# SparkFun_Uno_Qwiic_Mux_Shield_with_JST.net
KiCad netlist of a schematic drawn in EAGLE
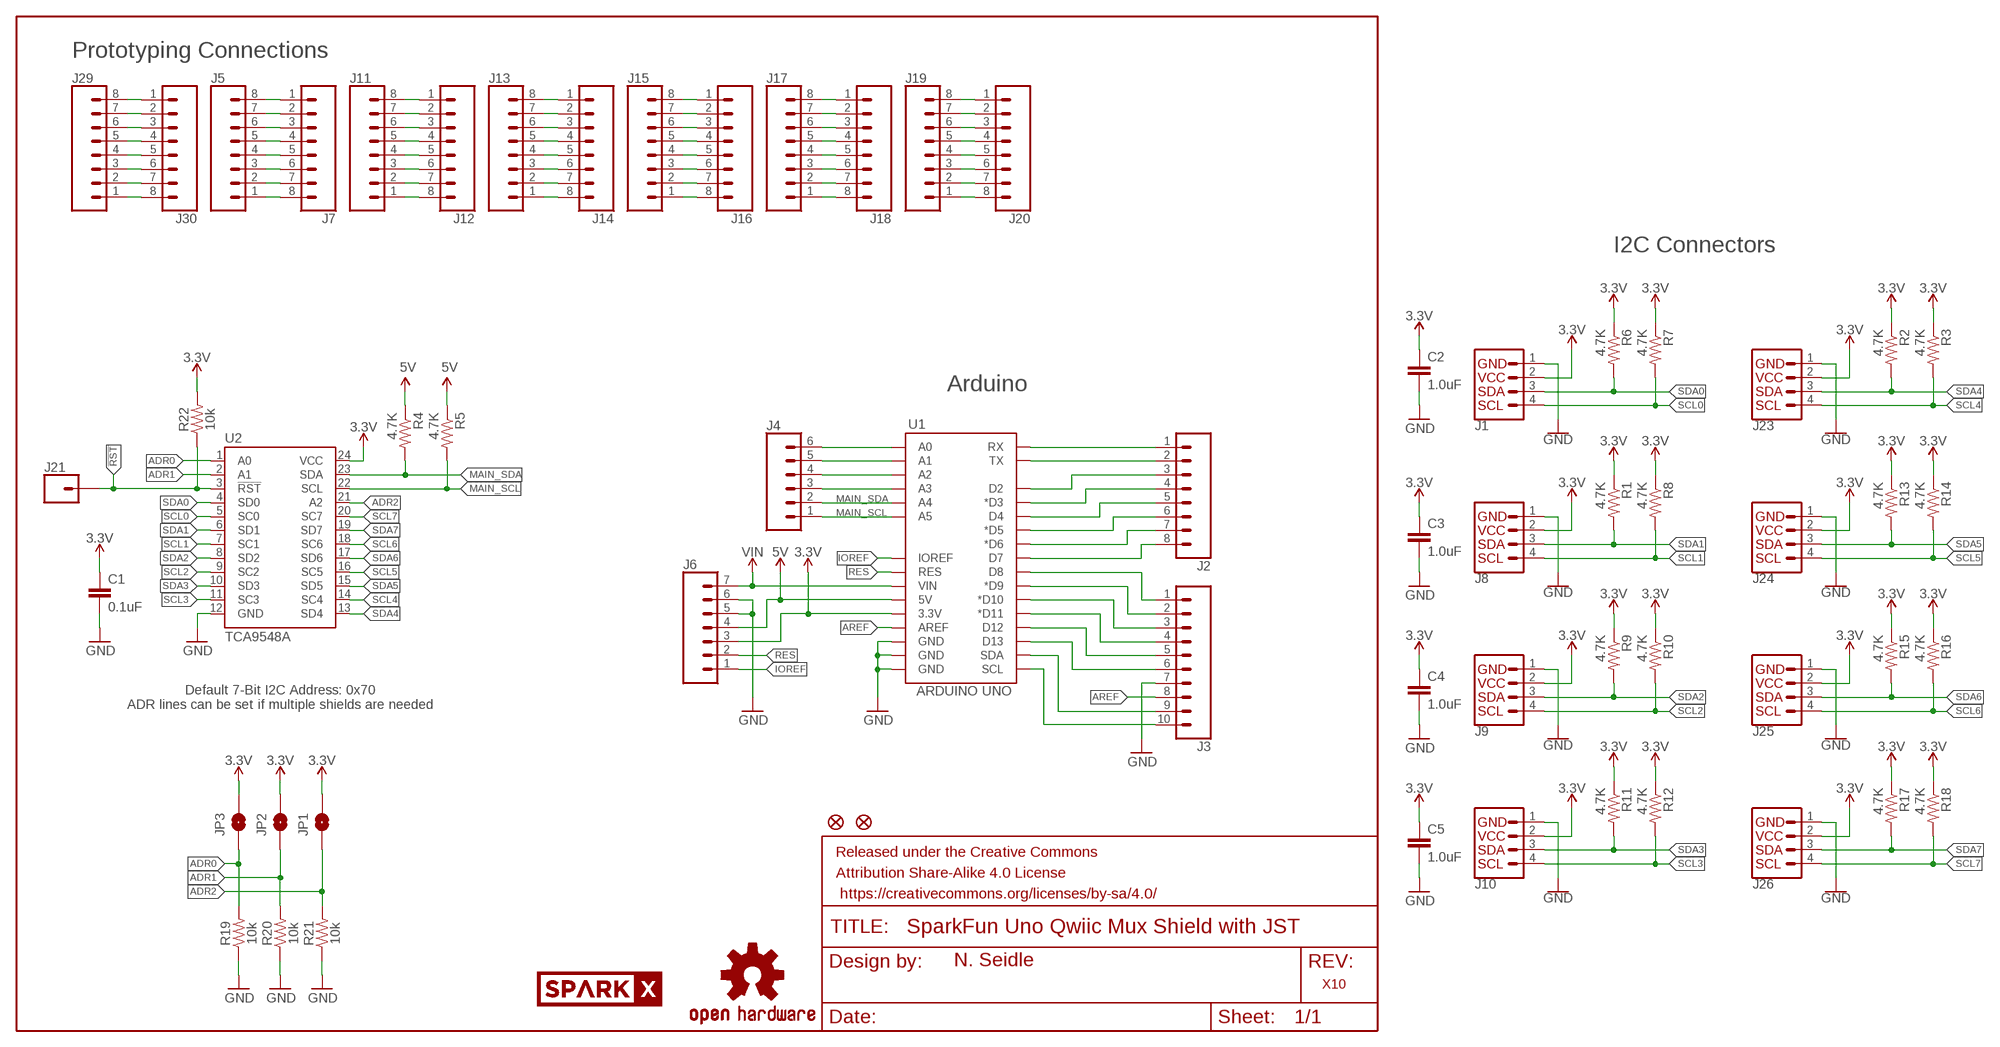
[diagram p0: schematic, sheet 1]

(export (version "E")
  (design (tool "Eeschema 10.0.6"))
  (components
    (comp (ref "C1")
      (value "0.1uF")
      (footprint "eagle-import:0603")
      (libsource (lib "eagle-import") (part "0.1UF-0603-25V-(+80/-20%)"))
    )
    (comp (ref "C2")
      (value "1.0uF")
      (footprint "eagle-import:0603")
      (libsource (lib "eagle-import") (part "1.0UF-0603-16V-10%"))
    )
    (comp (ref "C3")
      (value "1.0uF")
      (footprint "eagle-import:0603")
      (libsource (lib "eagle-import") (part "1.0UF-0603-16V-10%"))
    )
    (comp (ref "C4")
      (value "1.0uF")
      (footprint "eagle-import:0603")
      (libsource (lib "eagle-import") (part "1.0UF-0603-16V-10%"))
    )
    (comp (ref "C5")
      (value "1.0uF")
      (footprint "eagle-import:0603")
      (libsource (lib "eagle-import") (part "1.0UF-0603-16V-10%"))
    )
    (comp (ref "FD1")
      (value "FIDUCIAL1X2")
      (footprint "eagle-import:FIDUCIAL-1X2")
      (libsource (lib "eagle-import") (part "FIDUCIAL1X2"))
    )
    (comp (ref "FD2")
      (value "FIDUCIAL1X2")
      (footprint "eagle-import:FIDUCIAL-1X2")
      (libsource (lib "eagle-import") (part "FIDUCIAL1X2"))
    )
    (comp (ref "FRAME1")
      (value "FRAME-LETTER")
      (footprint "eagle-import:CREATIVE_COMMONS")
      (libsource (lib "eagle-import") (part "FRAME-LETTER"))
    )
    (comp (ref "J1")
      (value "I2C_STANDARDJS-1MM")
      (footprint "eagle-import:1X04_1MM_RA")
      (libsource (lib "eagle-import") (part "I2C_STANDARDJS-1MM"))
    )
    (comp (ref "J2")
      (value "CONN_08NO_SILK_FEMALE_PTH")
      (footprint "eagle-import:1X08_NO_SILK")
      (libsource (lib "eagle-import") (part "CONN_08NO_SILK_FEMALE_PTH"))
    )
    (comp (ref "J3")
      (value "CONN_10NO_SILK_PTH_FEMALE")
      (footprint "eagle-import:1X10_NO_SILK")
      (libsource (lib "eagle-import") (part "CONN_10NO_SILK_PTH_FEMALE"))
    )
    (comp (ref "J4")
      (value "CONN_06NO_SILK_FEMALE_PTH")
      (footprint "eagle-import:1X06_NO_SILK")
      (libsource (lib "eagle-import") (part "CONN_06NO_SILK_FEMALE_PTH"))
    )
    (comp (ref "J5")
      (value "CONN_08NO_SILK_FEMALE_PTH")
      (footprint "eagle-import:1X08_NO_SILK")
      (libsource (lib "eagle-import") (part "CONN_08NO_SILK_FEMALE_PTH"))
    )
    (comp (ref "J6")
      (value "CONN_07NO_SILK")
      (footprint "eagle-import:1X07_NO_SILK")
      (libsource (lib "eagle-import") (part "CONN_07NO_SILK"))
    )
    (comp (ref "J7")
      (value "CONN_08NO_SILK_FEMALE_PTH")
      (footprint "eagle-import:1X08_NO_SILK")
      (libsource (lib "eagle-import") (part "CONN_08NO_SILK_FEMALE_PTH"))
    )
    (comp (ref "J8")
      (value "I2C_STANDARDJS-1MM")
      (footprint "eagle-import:1X04_1MM_RA")
      (libsource (lib "eagle-import") (part "I2C_STANDARDJS-1MM"))
    )
    (comp (ref "J9")
      (value "I2C_STANDARDJS-1MM")
      (footprint "eagle-import:1X04_1MM_RA")
      (libsource (lib "eagle-import") (part "I2C_STANDARDJS-1MM"))
    )
    (comp (ref "J10")
      (value "I2C_STANDARDJS-1MM")
      (footprint "eagle-import:1X04_1MM_RA")
      (libsource (lib "eagle-import") (part "I2C_STANDARDJS-1MM"))
    )
    (comp (ref "J11")
      (value "CONN_08NO_SILK_FEMALE_PTH")
      (footprint "eagle-import:1X08_NO_SILK")
      (libsource (lib "eagle-import") (part "CONN_08NO_SILK_FEMALE_PTH"))
    )
    (comp (ref "J12")
      (value "CONN_08NO_SILK_FEMALE_PTH")
      (footprint "eagle-import:1X08_NO_SILK")
      (libsource (lib "eagle-import") (part "CONN_08NO_SILK_FEMALE_PTH"))
    )
    (comp (ref "J13")
      (value "CONN_08NO_SILK_FEMALE_PTH")
      (footprint "eagle-import:1X08_NO_SILK")
      (libsource (lib "eagle-import") (part "CONN_08NO_SILK_FEMALE_PTH"))
    )
    (comp (ref "J14")
      (value "CONN_08NO_SILK_FEMALE_PTH")
      (footprint "eagle-import:1X08_NO_SILK")
      (libsource (lib "eagle-import") (part "CONN_08NO_SILK_FEMALE_PTH"))
    )
    (comp (ref "J15")
      (value "CONN_08NO_SILK_FEMALE_PTH")
      (footprint "eagle-import:1X08_NO_SILK")
      (libsource (lib "eagle-import") (part "CONN_08NO_SILK_FEMALE_PTH"))
    )
    (comp (ref "J16")
      (value "CONN_08NO_SILK_FEMALE_PTH")
      (footprint "eagle-import:1X08_NO_SILK")
      (libsource (lib "eagle-import") (part "CONN_08NO_SILK_FEMALE_PTH"))
    )
    (comp (ref "J17")
      (value "CONN_08NO_SILK_FEMALE_PTH")
      (footprint "eagle-import:1X08_NO_SILK")
      (libsource (lib "eagle-import") (part "CONN_08NO_SILK_FEMALE_PTH"))
    )
    (comp (ref "J18")
      (value "CONN_08NO_SILK_FEMALE_PTH")
      (footprint "eagle-import:1X08_NO_SILK")
      (libsource (lib "eagle-import") (part "CONN_08NO_SILK_FEMALE_PTH"))
    )
    (comp (ref "J19")
      (value "CONN_08NO_SILK_FEMALE_PTH")
      (footprint "eagle-import:1X08_NO_SILK")
      (libsource (lib "eagle-import") (part "CONN_08NO_SILK_FEMALE_PTH"))
    )
    (comp (ref "J20")
      (value "CONN_08NO_SILK_FEMALE_PTH")
      (footprint "eagle-import:1X08_NO_SILK")
      (libsource (lib "eagle-import") (part "CONN_08NO_SILK_FEMALE_PTH"))
    )
    (comp (ref "J21")
      (value "CONN_01")
      (footprint "eagle-import:1X01")
      (libsource (lib "eagle-import") (part "CONN_01"))
    )
    (comp (ref "J23")
      (value "I2C_STANDARDSILK")
      (footprint "eagle-import:1X04")
      (libsource (lib "eagle-import") (part "I2C_STANDARDSILK"))
    )
    (comp (ref "J24")
      (value "I2C_STANDARDSILK")
      (footprint "eagle-import:1X04")
      (libsource (lib "eagle-import") (part "I2C_STANDARDSILK"))
    )
    (comp (ref "J25")
      (value "I2C_STANDARDSILK")
      (footprint "eagle-import:1X04")
      (libsource (lib "eagle-import") (part "I2C_STANDARDSILK"))
    )
    (comp (ref "J26")
      (value "I2C_STANDARDSILK")
      (footprint "eagle-import:1X04")
      (libsource (lib "eagle-import") (part "I2C_STANDARDSILK"))
    )
    (comp (ref "J29")
      (value "CONN_08NO_SILK_FEMALE_PTH")
      (footprint "eagle-import:1X08_NO_SILK")
      (libsource (lib "eagle-import") (part "CONN_08NO_SILK_FEMALE_PTH"))
    )
    (comp (ref "J30")
      (value "CONN_08NO_SILK_FEMALE_PTH")
      (footprint "eagle-import:1X08_NO_SILK")
      (libsource (lib "eagle-import") (part "CONN_08NO_SILK_FEMALE_PTH"))
    )
    (comp (ref "JP1")
      (value "JUMPER-SMT_2_NO_SILK")
      (footprint "eagle-import:SMT-JUMPER_2_NO_SILK")
      (libsource (lib "eagle-import") (part "JUMPER-SMT_2_NO_SILK"))
    )
    (comp (ref "JP2")
      (value "JUMPER-SMT_2_NO_SILK")
      (footprint "eagle-import:SMT-JUMPER_2_NO_SILK")
      (libsource (lib "eagle-import") (part "JUMPER-SMT_2_NO_SILK"))
    )
    (comp (ref "JP3")
      (value "JUMPER-SMT_2_NO_SILK")
      (footprint "eagle-import:SMT-JUMPER_2_NO_SILK")
      (libsource (lib "eagle-import") (part "JUMPER-SMT_2_NO_SILK"))
    )
    (comp (ref "LOGO1")
      (value "OSHW-LOGOMINI")
      (footprint "eagle-import:OSHW-LOGO-MINI")
      (libsource (lib "eagle-import") (part "OSHW-LOGOMINI"))
    )
    (comp (ref "R1")
      (value "4.7K")
      (footprint "eagle-import:0603-RES")
      (libsource (lib "eagle-import") (part "4.7KOHM-1/10W-1%(0603)"))
    )
    (comp (ref "R2")
      (value "4.7K")
      (footprint "eagle-import:0603-RES")
      (libsource (lib "eagle-import") (part "4.7KOHM-1/10W-1%(0603)"))
    )
    (comp (ref "R3")
      (value "4.7K")
      (footprint "eagle-import:0603-RES")
      (libsource (lib "eagle-import") (part "4.7KOHM-1/10W-1%(0603)"))
    )
    (comp (ref "R4")
      (value "4.7K")
      (footprint "eagle-import:0603-RES")
      (libsource (lib "eagle-import") (part "4.7KOHM-1/10W-1%(0603)"))
    )
    (comp (ref "R5")
      (value "4.7K")
      (footprint "eagle-import:0603-RES")
      (libsource (lib "eagle-import") (part "4.7KOHM-1/10W-1%(0603)"))
    )
    (comp (ref "R6")
      (value "4.7K")
      (footprint "eagle-import:0603-RES")
      (libsource (lib "eagle-import") (part "4.7KOHM-1/10W-1%(0603)"))
    )
    (comp (ref "R7")
      (value "4.7K")
      (footprint "eagle-import:0603-RES")
      (libsource (lib "eagle-import") (part "4.7KOHM-1/10W-1%(0603)"))
    )
    (comp (ref "R8")
      (value "4.7K")
      (footprint "eagle-import:0603-RES")
      (libsource (lib "eagle-import") (part "4.7KOHM-1/10W-1%(0603)"))
    )
    (comp (ref "R9")
      (value "4.7K")
      (footprint "eagle-import:0603-RES")
      (libsource (lib "eagle-import") (part "4.7KOHM-1/10W-1%(0603)"))
    )
    (comp (ref "R10")
      (value "4.7K")
      (footprint "eagle-import:0603-RES")
      (libsource (lib "eagle-import") (part "4.7KOHM-1/10W-1%(0603)"))
    )
    (comp (ref "R11")
      (value "4.7K")
      (footprint "eagle-import:0603-RES")
      (libsource (lib "eagle-import") (part "4.7KOHM-1/10W-1%(0603)"))
    )
    (comp (ref "R12")
      (value "4.7K")
      (footprint "eagle-import:0603-RES")
      (libsource (lib "eagle-import") (part "4.7KOHM-1/10W-1%(0603)"))
    )
    (comp (ref "R13")
      (value "4.7K")
      (footprint "eagle-import:0603-RES")
      (libsource (lib "eagle-import") (part "4.7KOHM-1/10W-1%(0603)"))
    )
    (comp (ref "R14")
      (value "4.7K")
      (footprint "eagle-import:0603-RES")
      (libsource (lib "eagle-import") (part "4.7KOHM-1/10W-1%(0603)"))
    )
    (comp (ref "R15")
      (value "4.7K")
      (footprint "eagle-import:0603-RES")
      (libsource (lib "eagle-import") (part "4.7KOHM-1/10W-1%(0603)"))
    )
    (comp (ref "R16")
      (value "4.7K")
      (footprint "eagle-import:0603-RES")
      (libsource (lib "eagle-import") (part "4.7KOHM-1/10W-1%(0603)"))
    )
    (comp (ref "R17")
      (value "4.7K")
      (footprint "eagle-import:0603-RES")
      (libsource (lib "eagle-import") (part "4.7KOHM-1/10W-1%(0603)"))
    )
    (comp (ref "R18")
      (value "4.7K")
      (footprint "eagle-import:0603-RES")
      (libsource (lib "eagle-import") (part "4.7KOHM-1/10W-1%(0603)"))
    )
    (comp (ref "R19")
      (value "10k")
      (footprint "eagle-import:0603")
      (libsource (lib "eagle-import") (part "10KOHM-0603-1/10W-1%"))
    )
    (comp (ref "R20")
      (value "10k")
      (footprint "eagle-import:0603")
      (libsource (lib "eagle-import") (part "10KOHM-0603-1/10W-1%"))
    )
    (comp (ref "R21")
      (value "10k")
      (footprint "eagle-import:0603")
      (libsource (lib "eagle-import") (part "10KOHM-0603-1/10W-1%"))
    )
    (comp (ref "R22")
      (value "10k")
      (footprint "eagle-import:0603")
      (libsource (lib "eagle-import") (part "10KOHM-0603-1/10W-1%"))
    )
    (comp (ref "U$1")
      (value "SPARKX-LOGO3")
      (footprint "eagle-import:SPARKX-SMALL")
      (libsource (lib "eagle-import") (part "SPARKX-LOGO3"))
    )
    (comp (ref "U$2")
      (value "SPARKX-LOGO5")
      (footprint "eagle-import:SPARKX-LARGE")
      (libsource (lib "eagle-import") (part "SPARKX-LOGO5"))
    )
    (comp (ref "U1")
      (value "ARDUINO UNO")
      (footprint "eagle-import:UNO_R3_SHIELD_NOLABELS")
      (libsource (lib "eagle-import") (part "ARDUINO_R3_SHIELDNOLABELS"))
    )
    (comp (ref "U2")
      (value "TCA9548A")
      (footprint "eagle-import:TSSOP28")
      (libsource (lib "eagle-import") (part "TCA9548A"))
    )
  )
  (nets
    (net (code "1") (name "/~{RST}") (class "Default")
      (node (ref "J21") (pin "1") (pinfunction "1_1") (pintype "passive"))
      (node (ref "R22") (pin "1") (pinfunction "1_1") (pintype "passive"))
      (node (ref "U2") (pin "3") (pinfunction "~{RST}_3") (pintype "bidirectional"))
    )
    (net (code "2") (name "3.3V") (class "Default")
      (node (ref "C1") (pin "1") (pinfunction "1_1") (pintype "passive"))
      (node (ref "C2") (pin "1") (pinfunction "1_1") (pintype "passive"))
      (node (ref "C3") (pin "1") (pinfunction "1_1") (pintype "passive"))
      (node (ref "C4") (pin "1") (pinfunction "1_1") (pintype "passive"))
      (node (ref "C5") (pin "1") (pinfunction "1_1") (pintype "passive"))
      (node (ref "J1") (pin "2") (pinfunction "VCC_2") (pintype "power_in"))
      (node (ref "J10") (pin "2") (pinfunction "VCC_2") (pintype "power_in"))
      (node (ref "J23") (pin "2") (pinfunction "VCC_2") (pintype "power_in"))
      (node (ref "J24") (pin "2") (pinfunction "VCC_2") (pintype "power_in"))
      (node (ref "J25") (pin "2") (pinfunction "VCC_2") (pintype "power_in"))
      (node (ref "J26") (pin "2") (pinfunction "VCC_2") (pintype "power_in"))
      (node (ref "J6") (pin "3") (pinfunction "3_3") (pintype "passive"))
      (node (ref "J8") (pin "2") (pinfunction "VCC_2") (pintype "power_in"))
      (node (ref "J9") (pin "2") (pinfunction "VCC_2") (pintype "power_in"))
      (node (ref "JP1") (pin "2") (pinfunction "2_2") (pintype "passive"))
      (node (ref "JP2") (pin "2") (pinfunction "2_2") (pintype "passive"))
      (node (ref "JP3") (pin "2") (pinfunction "2_2") (pintype "passive"))
      (node (ref "R1") (pin "1") (pinfunction "1_1") (pintype "passive"))
      (node (ref "R10") (pin "1") (pinfunction "1_1") (pintype "passive"))
      (node (ref "R11") (pin "1") (pinfunction "1_1") (pintype "passive"))
      (node (ref "R12") (pin "1") (pinfunction "1_1") (pintype "passive"))
      (node (ref "R13") (pin "1") (pinfunction "1_1") (pintype "passive"))
      (node (ref "R14") (pin "1") (pinfunction "1_1") (pintype "passive"))
      (node (ref "R15") (pin "1") (pinfunction "1_1") (pintype "passive"))
      (node (ref "R16") (pin "1") (pinfunction "1_1") (pintype "passive"))
      (node (ref "R17") (pin "1") (pinfunction "1_1") (pintype "passive"))
      (node (ref "R18") (pin "1") (pinfunction "1_1") (pintype "passive"))
      (node (ref "R2") (pin "1") (pinfunction "1_1") (pintype "passive"))
      (node (ref "R22") (pin "2") (pinfunction "2_2") (pintype "passive"))
      (node (ref "R3") (pin "1") (pinfunction "1_1") (pintype "passive"))
      (node (ref "R6") (pin "1") (pinfunction "1_1") (pintype "passive"))
      (node (ref "R7") (pin "1") (pinfunction "1_1") (pintype "passive"))
      (node (ref "R8") (pin "1") (pinfunction "1_1") (pintype "passive"))
      (node (ref "R9") (pin "1") (pinfunction "1_1") (pintype "passive"))
      (node (ref "U1") (pin "3.3V") (pinfunction "3.3V_3.3V") (pintype "bidirectional"))
      (node (ref "U2") (pin "24") (pinfunction "VCC_24") (pintype "bidirectional"))
    )
    (net (code "3") (name "5V") (class "Default")
      (node (ref "J6") (pin "4") (pinfunction "4_4") (pintype "passive"))
      (node (ref "R4") (pin "1") (pinfunction "1_1") (pintype "passive"))
      (node (ref "R5") (pin "1") (pinfunction "1_1") (pintype "passive"))
      (node (ref "U1") (pin "5V") (pinfunction "5V_5V") (pintype "bidirectional"))
    )
    (net (code "4") (name "ADR0") (class "Default")
      (node (ref "JP3") (pin "1") (pinfunction "1_1") (pintype "passive"))
      (node (ref "R19") (pin "2") (pinfunction "2_2") (pintype "passive"))
      (node (ref "U2") (pin "1") (pinfunction "A0_1") (pintype "bidirectional"))
    )
    (net (code "5") (name "ADR1") (class "Default")
      (node (ref "JP2") (pin "1") (pinfunction "1_1") (pintype "passive"))
      (node (ref "R20") (pin "2") (pinfunction "2_2") (pintype "passive"))
      (node (ref "U2") (pin "2") (pinfunction "A1_2") (pintype "bidirectional"))
    )
    (net (code "6") (name "ADR2") (class "Default")
      (node (ref "JP1") (pin "1") (pinfunction "1_1") (pintype "passive"))
      (node (ref "R21") (pin "2") (pinfunction "2_2") (pintype "passive"))
      (node (ref "U2") (pin "21") (pinfunction "A2_21") (pintype "bidirectional"))
    )
    (net (code "7") (name "AREF") (class "Default")
      (node (ref "J3") (pin "8") (pinfunction "8_8") (pintype "passive"))
      (node (ref "U1") (pin "AREF") (pinfunction "AREF_AREF") (pintype "bidirectional"))
    )
    (net (code "8") (name "GND") (class "Default")
      (node (ref "C1") (pin "2") (pinfunction "2_2") (pintype "passive"))
      (node (ref "C2") (pin "2") (pinfunction "2_2") (pintype "passive"))
      (node (ref "C3") (pin "2") (pinfunction "2_2") (pintype "passive"))
      (node (ref "C4") (pin "2") (pinfunction "2_2") (pintype "passive"))
      (node (ref "C5") (pin "2") (pinfunction "2_2") (pintype "passive"))
      (node (ref "J1") (pin "1") (pinfunction "GND_1") (pintype "power_in"))
      (node (ref "J10") (pin "1") (pinfunction "GND_1") (pintype "power_in"))
      (node (ref "J23") (pin "1") (pinfunction "GND_1") (pintype "power_in"))
      (node (ref "J24") (pin "1") (pinfunction "GND_1") (pintype "power_in"))
      (node (ref "J25") (pin "1") (pinfunction "GND_1") (pintype "power_in"))
      (node (ref "J26") (pin "1") (pinfunction "GND_1") (pintype "power_in"))
      (node (ref "J3") (pin "7") (pinfunction "7_7") (pintype "passive"))
      (node (ref "J6") (pin "5") (pinfunction "5_5") (pintype "passive"))
      (node (ref "J6") (pin "6") (pinfunction "6_6") (pintype "passive"))
      (node (ref "J8") (pin "1") (pinfunction "GND_1") (pintype "power_in"))
      (node (ref "J9") (pin "1") (pinfunction "GND_1") (pintype "power_in"))
      (node (ref "R19") (pin "1") (pinfunction "1_1") (pintype "passive"))
      (node (ref "R20") (pin "1") (pinfunction "1_1") (pintype "passive"))
      (node (ref "R21") (pin "1") (pinfunction "1_1") (pintype "passive"))
      (node (ref "U1") (pin "GND@0") (pinfunction "GND_GND@0") (pintype "bidirectional"))
      (node (ref "U1") (pin "GND@1") (pinfunction "GND_GND@1") (pintype "bidirectional"))
      (node (ref "U1") (pin "GND@2") (pinfunction "GND_GND@2") (pintype "bidirectional"))
      (node (ref "U2") (pin "12") (pinfunction "GND_12") (pintype "bidirectional"))
    )
    (net (code "9") (name "IOREF") (class "Default")
      (node (ref "J6") (pin "1") (pinfunction "1_1") (pintype "passive"))
      (node (ref "U1") (pin "IOREF") (pinfunction "IOREF_IOREF") (pintype "bidirectional"))
    )
    (net (code "10") (name "MAIN_SCL") (class "Default")
      (node (ref "J4") (pin "1") (pinfunction "1_1") (pintype "passive"))
      (node (ref "R5") (pin "2") (pinfunction "2_2") (pintype "passive"))
      (node (ref "U1") (pin "A5") (pinfunction "A5_A5") (pintype "bidirectional"))
      (node (ref "U2") (pin "22") (pinfunction "SCL_22") (pintype "bidirectional"))
    )
    (net (code "11") (name "MAIN_SDA") (class "Default")
      (node (ref "J4") (pin "2") (pinfunction "2_2") (pintype "passive"))
      (node (ref "R4") (pin "2") (pinfunction "2_2") (pintype "passive"))
      (node (ref "U1") (pin "A4") (pinfunction "A4_A4") (pintype "bidirectional"))
      (node (ref "U2") (pin "23") (pinfunction "SDA_23") (pintype "bidirectional"))
    )
    (net (code "12") (name "Net-(J2-Pad1)") (class "Default")
      (node (ref "J2") (pin "1") (pinfunction "1_1") (pintype "passive"))
      (node (ref "U1") (pin "RX") (pinfunction "RX_RX") (pintype "bidirectional"))
    )
    (net (code "13") (name "Net-(J2-Pad2)") (class "Default")
      (node (ref "J2") (pin "2") (pinfunction "2_2") (pintype "passive"))
      (node (ref "U1") (pin "TX") (pinfunction "TX_TX") (pintype "bidirectional"))
    )
    (net (code "14") (name "Net-(J2-Pad3)") (class "Default")
      (node (ref "J2") (pin "3") (pinfunction "3_3") (pintype "passive"))
      (node (ref "U1") (pin "D2") (pinfunction "D2_D2") (pintype "bidirectional"))
    )
    (net (code "15") (name "Net-(J2-Pad5)") (class "Default")
      (node (ref "J2") (pin "5") (pinfunction "5_5") (pintype "passive"))
      (node (ref "U1") (pin "D4") (pinfunction "D4_D4") (pintype "bidirectional"))
    )
    (net (code "16") (name "Net-(J2-Pad8)") (class "Default")
      (node (ref "J2") (pin "8") (pinfunction "8_8") (pintype "passive"))
      (node (ref "U1") (pin "D7") (pinfunction "D7_D7") (pintype "bidirectional"))
    )
    (net (code "17") (name "Net-(J3-Pad1)") (class "Default")
      (node (ref "J3") (pin "1") (pinfunction "1_1") (pintype "passive"))
      (node (ref "U1") (pin "D8") (pinfunction "D8_D8") (pintype "bidirectional"))
    )
    (net (code "18") (name "Net-(J3-Pad5)") (class "Default")
      (node (ref "J3") (pin "5") (pinfunction "5_5") (pintype "passive"))
      (node (ref "U1") (pin "D12") (pinfunction "D12_D12") (pintype "bidirectional"))
    )
    (net (code "19") (name "Net-(J3-Pad6)") (class "Default")
      (node (ref "J3") (pin "6") (pinfunction "6_6") (pintype "passive"))
      (node (ref "U1") (pin "D13") (pinfunction "D13_D13") (pintype "bidirectional"))
    )
    (net (code "20") (name "Net-(J3-Pad9)") (class "Default")
      (node (ref "J3") (pin "9") (pinfunction "9_9") (pintype "passive"))
      (node (ref "U1") (pin "SDA") (pinfunction "SDA_SDA") (pintype "bidirectional"))
    )
    (net (code "21") (name "Net-(J3-Pad10)") (class "Default")
      (node (ref "J3") (pin "10") (pinfunction "10_10") (pintype "passive"))
      (node (ref "U1") (pin "SCL") (pinfunction "SCL_SCL") (pintype "bidirectional"))
    )
    (net (code "22") (name "Net-(J4-Pad3)") (class "Default")
      (node (ref "J4") (pin "3") (pinfunction "3_3") (pintype "passive"))
      (node (ref "U1") (pin "A3") (pinfunction "A3_A3") (pintype "bidirectional"))
    )
    (net (code "23") (name "Net-(J4-Pad4)") (class "Default")
      (node (ref "J4") (pin "4") (pinfunction "4_4") (pintype "passive"))
      (node (ref "U1") (pin "A2") (pinfunction "A2_A2") (pintype "bidirectional"))
    )
    (net (code "24") (name "Net-(J4-Pad5)") (class "Default")
      (node (ref "J4") (pin "5") (pinfunction "5_5") (pintype "passive"))
      (node (ref "U1") (pin "A1") (pinfunction "A1_A1") (pintype "bidirectional"))
    )
    (net (code "25") (name "Net-(J4-Pad6)") (class "Default")
      (node (ref "J4") (pin "6") (pinfunction "6_6") (pintype "passive"))
      (node (ref "U1") (pin "A0") (pinfunction "A0_A0") (pintype "bidirectional"))
    )
    (net (code "26") (name "Net-(J5-Pad1)") (class "Default")
      (node (ref "J5") (pin "1") (pinfunction "1_1") (pintype "passive"))
      (node (ref "J7") (pin "8") (pinfunction "8_8") (pintype "passive"))
    )
    (net (code "27") (name "Net-(J5-Pad2)") (class "Default")
      (node (ref "J5") (pin "2") (pinfunction "2_2") (pintype "passive"))
      (node (ref "J7") (pin "7") (pinfunction "7_7") (pintype "passive"))
    )
    (net (code "28") (name "Net-(J5-Pad3)") (class "Default")
      (node (ref "J5") (pin "3") (pinfunction "3_3") (pintype "passive"))
      (node (ref "J7") (pin "6") (pinfunction "6_6") (pintype "passive"))
    )
    (net (code "29") (name "Net-(J5-Pad4)") (class "Default")
      (node (ref "J5") (pin "4") (pinfunction "4_4") (pintype "passive"))
      (node (ref "J7") (pin "5") (pinfunction "5_5") (pintype "passive"))
    )
    (net (code "30") (name "Net-(J5-Pad5)") (class "Default")
      (node (ref "J5") (pin "5") (pinfunction "5_5") (pintype "passive"))
      (node (ref "J7") (pin "4") (pinfunction "4_4") (pintype "passive"))
    )
    (net (code "31") (name "Net-(J5-Pad6)") (class "Default")
      (node (ref "J5") (pin "6") (pinfunction "6_6") (pintype "passive"))
      (node (ref "J7") (pin "3") (pinfunction "3_3") (pintype "passive"))
    )
    (net (code "32") (name "Net-(J5-Pad7)") (class "Default")
      (node (ref "J5") (pin "7") (pinfunction "7_7") (pintype "passive"))
      (node (ref "J7") (pin "2") (pinfunction "2_2") (pintype "passive"))
    )
    (net (code "33") (name "Net-(J5-Pad8)") (class "Default")
      (node (ref "J5") (pin "8") (pinfunction "8_8") (pintype "passive"))
      (node (ref "J7") (pin "1") (pinfunction "1_1") (pintype "passive"))
    )
    (net (code "34") (name "Net-(J11-Pad1)") (class "Default")
      (node (ref "J11") (pin "1") (pinfunction "1_1") (pintype "passive"))
      (node (ref "J12") (pin "8") (pinfunction "8_8") (pintype "passive"))
    )
    (net (code "35") (name "Net-(J11-Pad2)") (class "Default")
      (node (ref "J11") (pin "2") (pinfunction "2_2") (pintype "passive"))
      (node (ref "J12") (pin "7") (pinfunction "7_7") (pintype "passive"))
    )
    (net (code "36") (name "Net-(J11-Pad3)") (class "Default")
      (node (ref "J11") (pin "3") (pinfunction "3_3") (pintype "passive"))
      (node (ref "J12") (pin "6") (pinfunction "6_6") (pintype "passive"))
    )
    (net (code "37") (name "Net-(J11-Pad4)") (class "Default")
      (node (ref "J11") (pin "4") (pinfunction "4_4") (pintype "passive"))
      (node (ref "J12") (pin "5") (pinfunction "5_5") (pintype "passive"))
    )
    (net (code "38") (name "Net-(J11-Pad5)") (class "Default")
      (node (ref "J11") (pin "5") (pinfunction "5_5") (pintype "passive"))
      (node (ref "J12") (pin "4") (pinfunction "4_4") (pintype "passive"))
    )
    (net (code "39") (name "Net-(J11-Pad6)") (class "Default")
      (node (ref "J11") (pin "6") (pinfunction "6_6") (pintype "passive"))
      (node (ref "J12") (pin "3") (pinfunction "3_3") (pintype "passive"))
    )
    (net (code "40") (name "Net-(J11-Pad7)") (class "Default")
      (node (ref "J11") (pin "7") (pinfunction "7_7") (pintype "passive"))
      (node (ref "J12") (pin "2") (pinfunction "2_2") (pintype "passive"))
    )
    (net (code "41") (name "Net-(J11-Pad8)") (class "Default")
      (node (ref "J11") (pin "8") (pinfunction "8_8") (pintype "passive"))
      (node (ref "J12") (pin "1") (pinfunction "1_1") (pintype "passive"))
    )
    (net (code "42") (name "Net-(J13-Pad1)") (class "Default")
      (node (ref "J13") (pin "1") (pinfunction "1_1") (pintype "passive"))
      (node (ref "J14") (pin "8") (pinfunction "8_8") (pintype "passive"))
    )
    (net (code "43") (name "Net-(J13-Pad2)") (class "Default")
      (node (ref "J13") (pin "2") (pinfunction "2_2") (pintype "passive"))
      (node (ref "J14") (pin "7") (pinfunction "7_7") (pintype "passive"))
    )
    (net (code "44") (name "Net-(J13-Pad3)") (class "Default")
      (node (ref "J13") (pin "3") (pinfunction "3_3") (pintype "passive"))
      (node (ref "J14") (pin "6") (pinfunction "6_6") (pintype "passive"))
    )
    (net (code "45") (name "Net-(J13-Pad4)") (class "Default")
      (node (ref "J13") (pin "4") (pinfunction "4_4") (pintype "passive"))
      (node (ref "J14") (pin "5") (pinfunction "5_5") (pintype "passive"))
    )
    (net (code "46") (name "Net-(J13-Pad5)") (class "Default")
      (node (ref "J13") (pin "5") (pinfunction "5_5") (pintype "passive"))
      (node (ref "J14") (pin "4") (pinfunction "4_4") (pintype "passive"))
    )
    (net (code "47") (name "Net-(J13-Pad6)") (class "Default")
      (node (ref "J13") (pin "6") (pinfunction "6_6") (pintype "passive"))
      (node (ref "J14") (pin "3") (pinfunction "3_3") (pintype "passive"))
    )
    (net (code "48") (name "Net-(J13-Pad7)") (class "Default")
      (node (ref "J13") (pin "7") (pinfunction "7_7") (pintype "passive"))
      (node (ref "J14") (pin "2") (pinfunction "2_2") (pintype "passive"))
    )
    (net (code "49") (name "Net-(J13-Pad8)") (class "Default")
      (node (ref "J13") (pin "8") (pinfunction "8_8") (pintype "passive"))
      (node (ref "J14") (pin "1") (pinfunction "1_1") (pintype "passive"))
    )
    (net (code "50") (name "Net-(J15-Pad1)") (class "Default")
      (node (ref "J15") (pin "1") (pinfunction "1_1") (pintype "passive"))
      (node (ref "J16") (pin "8") (pinfunction "8_8") (pintype "passive"))
    )
    (net (code "51") (name "Net-(J15-Pad2)") (class "Default")
      (node (ref "J15") (pin "2") (pinfunction "2_2") (pintype "passive"))
      (node (ref "J16") (pin "7") (pinfunction "7_7") (pintype "passive"))
    )
    (net (code "52") (name "Net-(J15-Pad3)") (class "Default")
      (node (ref "J15") (pin "3") (pinfunction "3_3") (pintype "passive"))
      (node (ref "J16") (pin "6") (pinfunction "6_6") (pintype "passive"))
    )
    (net (code "53") (name "Net-(J15-Pad4)") (class "Default")
      (node (ref "J15") (pin "4") (pinfunction "4_4") (pintype "passive"))
      (node (ref "J16") (pin "5") (pinfunction "5_5") (pintype "passive"))
    )
    (net (code "54") (name "Net-(J15-Pad5)") (class "Default")
      (node (ref "J15") (pin "5") (pinfunction "5_5") (pintype "passive"))
      (node (ref "J16") (pin "4") (pinfunction "4_4") (pintype "passive"))
    )
    (net (code "55") (name "Net-(J15-Pad6)") (class "Default")
      (node (ref "J15") (pin "6") (pinfunction "6_6") (pintype "passive"))
      (node (ref "J16") (pin "3") (pinfunction "3_3") (pintype "passive"))
    )
    (net (code "56") (name "Net-(J15-Pad7)") (class "Default")
      (node (ref "J15") (pin "7") (pinfunction "7_7") (pintype "passive"))
      (node (ref "J16") (pin "2") (pinfunction "2_2") (pintype "passive"))
    )
    (net (code "57") (name "Net-(J15-Pad8)") (class "Default")
      (node (ref "J15") (pin "8") (pinfunction "8_8") (pintype "passive"))
      (node (ref "J16") (pin "1") (pinfunction "1_1") (pintype "passive"))
    )
    (net (code "58") (name "Net-(J17-Pad1)") (class "Default")
      (node (ref "J17") (pin "1") (pinfunction "1_1") (pintype "passive"))
      (node (ref "J18") (pin "8") (pinfunction "8_8") (pintype "passive"))
    )
    (net (code "59") (name "Net-(J17-Pad2)") (class "Default")
      (node (ref "J17") (pin "2") (pinfunction "2_2") (pintype "passive"))
      (node (ref "J18") (pin "7") (pinfunction "7_7") (pintype "passive"))
    )
    (net (code "60") (name "Net-(J17-Pad3)") (class "Default")
      (node (ref "J17") (pin "3") (pinfunction "3_3") (pintype "passive"))
      (node (ref "J18") (pin "6") (pinfunction "6_6") (pintype "passive"))
    )
    (net (code "61") (name "Net-(J17-Pad4)") (class "Default")
      (node (ref "J17") (pin "4") (pinfunction "4_4") (pintype "passive"))
      (node (ref "J18") (pin "5") (pinfunction "5_5") (pintype "passive"))
    )
    (net (code "62") (name "Net-(J17-Pad5)") (class "Default")
      (node (ref "J17") (pin "5") (pinfunction "5_5") (pintype "passive"))
      (node (ref "J18") (pin "4") (pinfunction "4_4") (pintype "passive"))
    )
    (net (code "63") (name "Net-(J17-Pad6)") (class "Default")
      (node (ref "J17") (pin "6") (pinfunction "6_6") (pintype "passive"))
      (node (ref "J18") (pin "3") (pinfunction "3_3") (pintype "passive"))
    )
    (net (code "64") (name "Net-(J17-Pad7)") (class "Default")
      (node (ref "J17") (pin "7") (pinfunction "7_7") (pintype "passive"))
      (node (ref "J18") (pin "2") (pinfunction "2_2") (pintype "passive"))
    )
    (net (code "65") (name "Net-(J17-Pad8)") (class "Default")
      (node (ref "J17") (pin "8") (pinfunction "8_8") (pintype "passive"))
      (node (ref "J18") (pin "1") (pinfunction "1_1") (pintype "passive"))
    )
    (net (code "66") (name "Net-(J19-Pad1)") (class "Default")
      (node (ref "J19") (pin "1") (pinfunction "1_1") (pintype "passive"))
      (node (ref "J20") (pin "8") (pinfunction "8_8") (pintype "passive"))
    )
    (net (code "67") (name "Net-(J19-Pad2)") (class "Default")
      (node (ref "J19") (pin "2") (pinfunction "2_2") (pintype "passive"))
      (node (ref "J20") (pin "7") (pinfunction "7_7") (pintype "passive"))
    )
    (net (code "68") (name "Net-(J19-Pad3)") (class "Default")
      (node (ref "J19") (pin "3") (pinfunction "3_3") (pintype "passive"))
      (node (ref "J20") (pin "6") (pinfunction "6_6") (pintype "passive"))
    )
    (net (code "69") (name "Net-(J19-Pad4)") (class "Default")
      (node (ref "J19") (pin "4") (pinfunction "4_4") (pintype "passive"))
      (node (ref "J20") (pin "5") (pinfunction "5_5") (pintype "passive"))
    )
    (net (code "70") (name "Net-(J19-Pad5)") (class "Default")
      (node (ref "J19") (pin "5") (pinfunction "5_5") (pintype "passive"))
      (node (ref "J20") (pin "4") (pinfunction "4_4") (pintype "passive"))
    )
    (net (code "71") (name "Net-(J19-Pad6)") (class "Default")
      (node (ref "J19") (pin "6") (pinfunction "6_6") (pintype "passive"))
      (node (ref "J20") (pin "3") (pinfunction "3_3") (pintype "passive"))
    )
    (net (code "72") (name "Net-(J19-Pad7)") (class "Default")
      (node (ref "J19") (pin "7") (pinfunction "7_7") (pintype "passive"))
      (node (ref "J20") (pin "2") (pinfunction "2_2") (pintype "passive"))
    )
    (net (code "73") (name "Net-(J19-Pad8)") (class "Default")
      (node (ref "J19") (pin "8") (pinfunction "8_8") (pintype "passive"))
      (node (ref "J20") (pin "1") (pinfunction "1_1") (pintype "passive"))
    )
    (net (code "74") (name "Net-(J29-Pad1)") (class "Default")
      (node (ref "J29") (pin "1") (pinfunction "1_1") (pintype "passive"))
      (node (ref "J30") (pin "8") (pinfunction "8_8") (pintype "passive"))
    )
    (net (code "75") (name "Net-(J29-Pad2)") (class "Default")
      (node (ref "J29") (pin "2") (pinfunction "2_2") (pintype "passive"))
      (node (ref "J30") (pin "7") (pinfunction "7_7") (pintype "passive"))
    )
    (net (code "76") (name "Net-(J29-Pad3)") (class "Default")
      (node (ref "J29") (pin "3") (pinfunction "3_3") (pintype "passive"))
      (node (ref "J30") (pin "6") (pinfunction "6_6") (pintype "passive"))
    )
    (net (code "77") (name "Net-(J29-Pad4)") (class "Default")
      (node (ref "J29") (pin "4") (pinfunction "4_4") (pintype "passive"))
      (node (ref "J30") (pin "5") (pinfunction "5_5") (pintype "passive"))
    )
    (net (code "78") (name "Net-(J29-Pad5)") (class "Default")
      (node (ref "J29") (pin "5") (pinfunction "5_5") (pintype "passive"))
      (node (ref "J30") (pin "4") (pinfunction "4_4") (pintype "passive"))
    )
    (net (code "79") (name "Net-(J29-Pad6)") (class "Default")
      (node (ref "J29") (pin "6") (pinfunction "6_6") (pintype "passive"))
      (node (ref "J30") (pin "3") (pinfunction "3_3") (pintype "passive"))
    )
    (net (code "80") (name "Net-(J29-Pad7)") (class "Default")
      (node (ref "J29") (pin "7") (pinfunction "7_7") (pintype "passive"))
      (node (ref "J30") (pin "2") (pinfunction "2_2") (pintype "passive"))
    )
    (net (code "81") (name "Net-(J29-Pad8)") (class "Default")
      (node (ref "J29") (pin "8") (pinfunction "8_8") (pintype "passive"))
      (node (ref "J30") (pin "1") (pinfunction "1_1") (pintype "passive"))
    )
    (net (code "82") (name "Net-(U1-*D3)") (class "Default")
      (node (ref "J2") (pin "4") (pinfunction "4_4") (pintype "passive"))
      (node (ref "U1") (pin "D3") (pinfunction "*D3_D3") (pintype "bidirectional"))
    )
    (net (code "83") (name "Net-(U1-*D5)") (class "Default")
      (node (ref "J2") (pin "6") (pinfunction "6_6") (pintype "passive"))
      (node (ref "U1") (pin "D5") (pinfunction "*D5_D5") (pintype "bidirectional"))
    )
    (net (code "84") (name "Net-(U1-*D6)") (class "Default")
      (node (ref "J2") (pin "7") (pinfunction "7_7") (pintype "passive"))
      (node (ref "U1") (pin "D6") (pinfunction "*D6_D6") (pintype "bidirectional"))
    )
    (net (code "85") (name "Net-(U1-*D9)") (class "Default")
      (node (ref "J3") (pin "2") (pinfunction "2_2") (pintype "passive"))
      (node (ref "U1") (pin "D9") (pinfunction "*D9_D9") (pintype "bidirectional"))
    )
    (net (code "86") (name "Net-(U1-*D10)") (class "Default")
      (node (ref "J3") (pin "3") (pinfunction "3_3") (pintype "passive"))
      (node (ref "U1") (pin "D10") (pinfunction "*D10_D10") (pintype "bidirectional"))
    )
    (net (code "87") (name "Net-(U1-*D11)") (class "Default")
      (node (ref "J3") (pin "4") (pinfunction "4_4") (pintype "passive"))
      (node (ref "U1") (pin "D11") (pinfunction "*D11_D11") (pintype "bidirectional"))
    )
    (net (code "88") (name "RES") (class "Default")
      (node (ref "J6") (pin "2") (pinfunction "2_2") (pintype "passive"))
      (node (ref "U1") (pin "RES") (pinfunction "RES_RES") (pintype "bidirectional"))
    )
    (net (code "89") (name "SCL0") (class "Default")
      (node (ref "J1") (pin "4") (pinfunction "SCL_4") (pintype "passive"))
      (node (ref "R7") (pin "2") (pinfunction "2_2") (pintype "passive"))
      (node (ref "U2") (pin "5") (pinfunction "SC0_5") (pintype "bidirectional"))
    )
    (net (code "90") (name "SCL1") (class "Default")
      (node (ref "J8") (pin "4") (pinfunction "SCL_4") (pintype "passive"))
      (node (ref "R8") (pin "2") (pinfunction "2_2") (pintype "passive"))
      (node (ref "U2") (pin "7") (pinfunction "SC1_7") (pintype "bidirectional"))
    )
    (net (code "91") (name "SCL2") (class "Default")
      (node (ref "J9") (pin "4") (pinfunction "SCL_4") (pintype "passive"))
      (node (ref "R10") (pin "2") (pinfunction "2_2") (pintype "passive"))
      (node (ref "U2") (pin "9") (pinfunction "SC2_9") (pintype "bidirectional"))
    )
    (net (code "92") (name "SCL3") (class "Default")
      (node (ref "J10") (pin "4") (pinfunction "SCL_4") (pintype "passive"))
      (node (ref "R12") (pin "2") (pinfunction "2_2") (pintype "passive"))
      (node (ref "U2") (pin "11") (pinfunction "SC3_11") (pintype "bidirectional"))
    )
    (net (code "93") (name "SCL4") (class "Default")
      (node (ref "J23") (pin "4") (pinfunction "SCL_4") (pintype "passive"))
      (node (ref "R3") (pin "2") (pinfunction "2_2") (pintype "passive"))
      (node (ref "U2") (pin "14") (pinfunction "SC4_14") (pintype "bidirectional"))
    )
    (net (code "94") (name "SCL5") (class "Default")
      (node (ref "J24") (pin "4") (pinfunction "SCL_4") (pintype "passive"))
      (node (ref "R14") (pin "2") (pinfunction "2_2") (pintype "passive"))
      (node (ref "U2") (pin "16") (pinfunction "SC5_16") (pintype "bidirectional"))
    )
    (net (code "95") (name "SCL6") (class "Default")
      (node (ref "J25") (pin "4") (pinfunction "SCL_4") (pintype "passive"))
      (node (ref "R16") (pin "2") (pinfunction "2_2") (pintype "passive"))
      (node (ref "U2") (pin "18") (pinfunction "SC6_18") (pintype "bidirectional"))
    )
    (net (code "96") (name "SCL7") (class "Default")
      (node (ref "J26") (pin "4") (pinfunction "SCL_4") (pintype "passive"))
      (node (ref "R18") (pin "2") (pinfunction "2_2") (pintype "passive"))
      (node (ref "U2") (pin "20") (pinfunction "SC7_20") (pintype "bidirectional"))
    )
    (net (code "97") (name "SDA0") (class "Default")
      (node (ref "J1") (pin "3") (pinfunction "SDA_3") (pintype "passive"))
      (node (ref "R6") (pin "2") (pinfunction "2_2") (pintype "passive"))
      (node (ref "U2") (pin "4") (pinfunction "SD0_4") (pintype "bidirectional"))
    )
    (net (code "98") (name "SDA1") (class "Default")
      (node (ref "J8") (pin "3") (pinfunction "SDA_3") (pintype "passive"))
      (node (ref "R1") (pin "2") (pinfunction "2_2") (pintype "passive"))
      (node (ref "U2") (pin "6") (pinfunction "SD1_6") (pintype "bidirectional"))
    )
    (net (code "99") (name "SDA2") (class "Default")
      (node (ref "J9") (pin "3") (pinfunction "SDA_3") (pintype "passive"))
      (node (ref "R9") (pin "2") (pinfunction "2_2") (pintype "passive"))
      (node (ref "U2") (pin "8") (pinfunction "SD2_8") (pintype "bidirectional"))
    )
    (net (code "100") (name "SDA3") (class "Default")
      (node (ref "J10") (pin "3") (pinfunction "SDA_3") (pintype "passive"))
      (node (ref "R11") (pin "2") (pinfunction "2_2") (pintype "passive"))
      (node (ref "U2") (pin "10") (pinfunction "SD3_10") (pintype "bidirectional"))
    )
    (net (code "101") (name "SDA4") (class "Default")
      (node (ref "J23") (pin "3") (pinfunction "SDA_3") (pintype "passive"))
      (node (ref "R2") (pin "2") (pinfunction "2_2") (pintype "passive"))
      (node (ref "U2") (pin "13") (pinfunction "SD4_13") (pintype "bidirectional"))
    )
    (net (code "102") (name "SDA5") (class "Default")
      (node (ref "J24") (pin "3") (pinfunction "SDA_3") (pintype "passive"))
      (node (ref "R13") (pin "2") (pinfunction "2_2") (pintype "passive"))
      (node (ref "U2") (pin "15") (pinfunction "SD5_15") (pintype "bidirectional"))
    )
    (net (code "103") (name "SDA6") (class "Default")
      (node (ref "J25") (pin "3") (pinfunction "SDA_3") (pintype "passive"))
      (node (ref "R15") (pin "2") (pinfunction "2_2") (pintype "passive"))
      (node (ref "U2") (pin "17") (pinfunction "SD6_17") (pintype "bidirectional"))
    )
    (net (code "104") (name "SDA7") (class "Default")
      (node (ref "J26") (pin "3") (pinfunction "SDA_3") (pintype "passive"))
      (node (ref "R17") (pin "2") (pinfunction "2_2") (pintype "passive"))
      (node (ref "U2") (pin "19") (pinfunction "SD7_19") (pintype "bidirectional"))
    )
    (net (code "105") (name "VIN") (class "Default")
      (node (ref "J6") (pin "7") (pinfunction "7_7") (pintype "passive"))
      (node (ref "U1") (pin "VIN") (pinfunction "VIN_VIN") (pintype "bidirectional"))
    )
  )
)
